# 3-channel_geo_amplifier.net
KiCad netlist of a schematic drawn in EAGLE
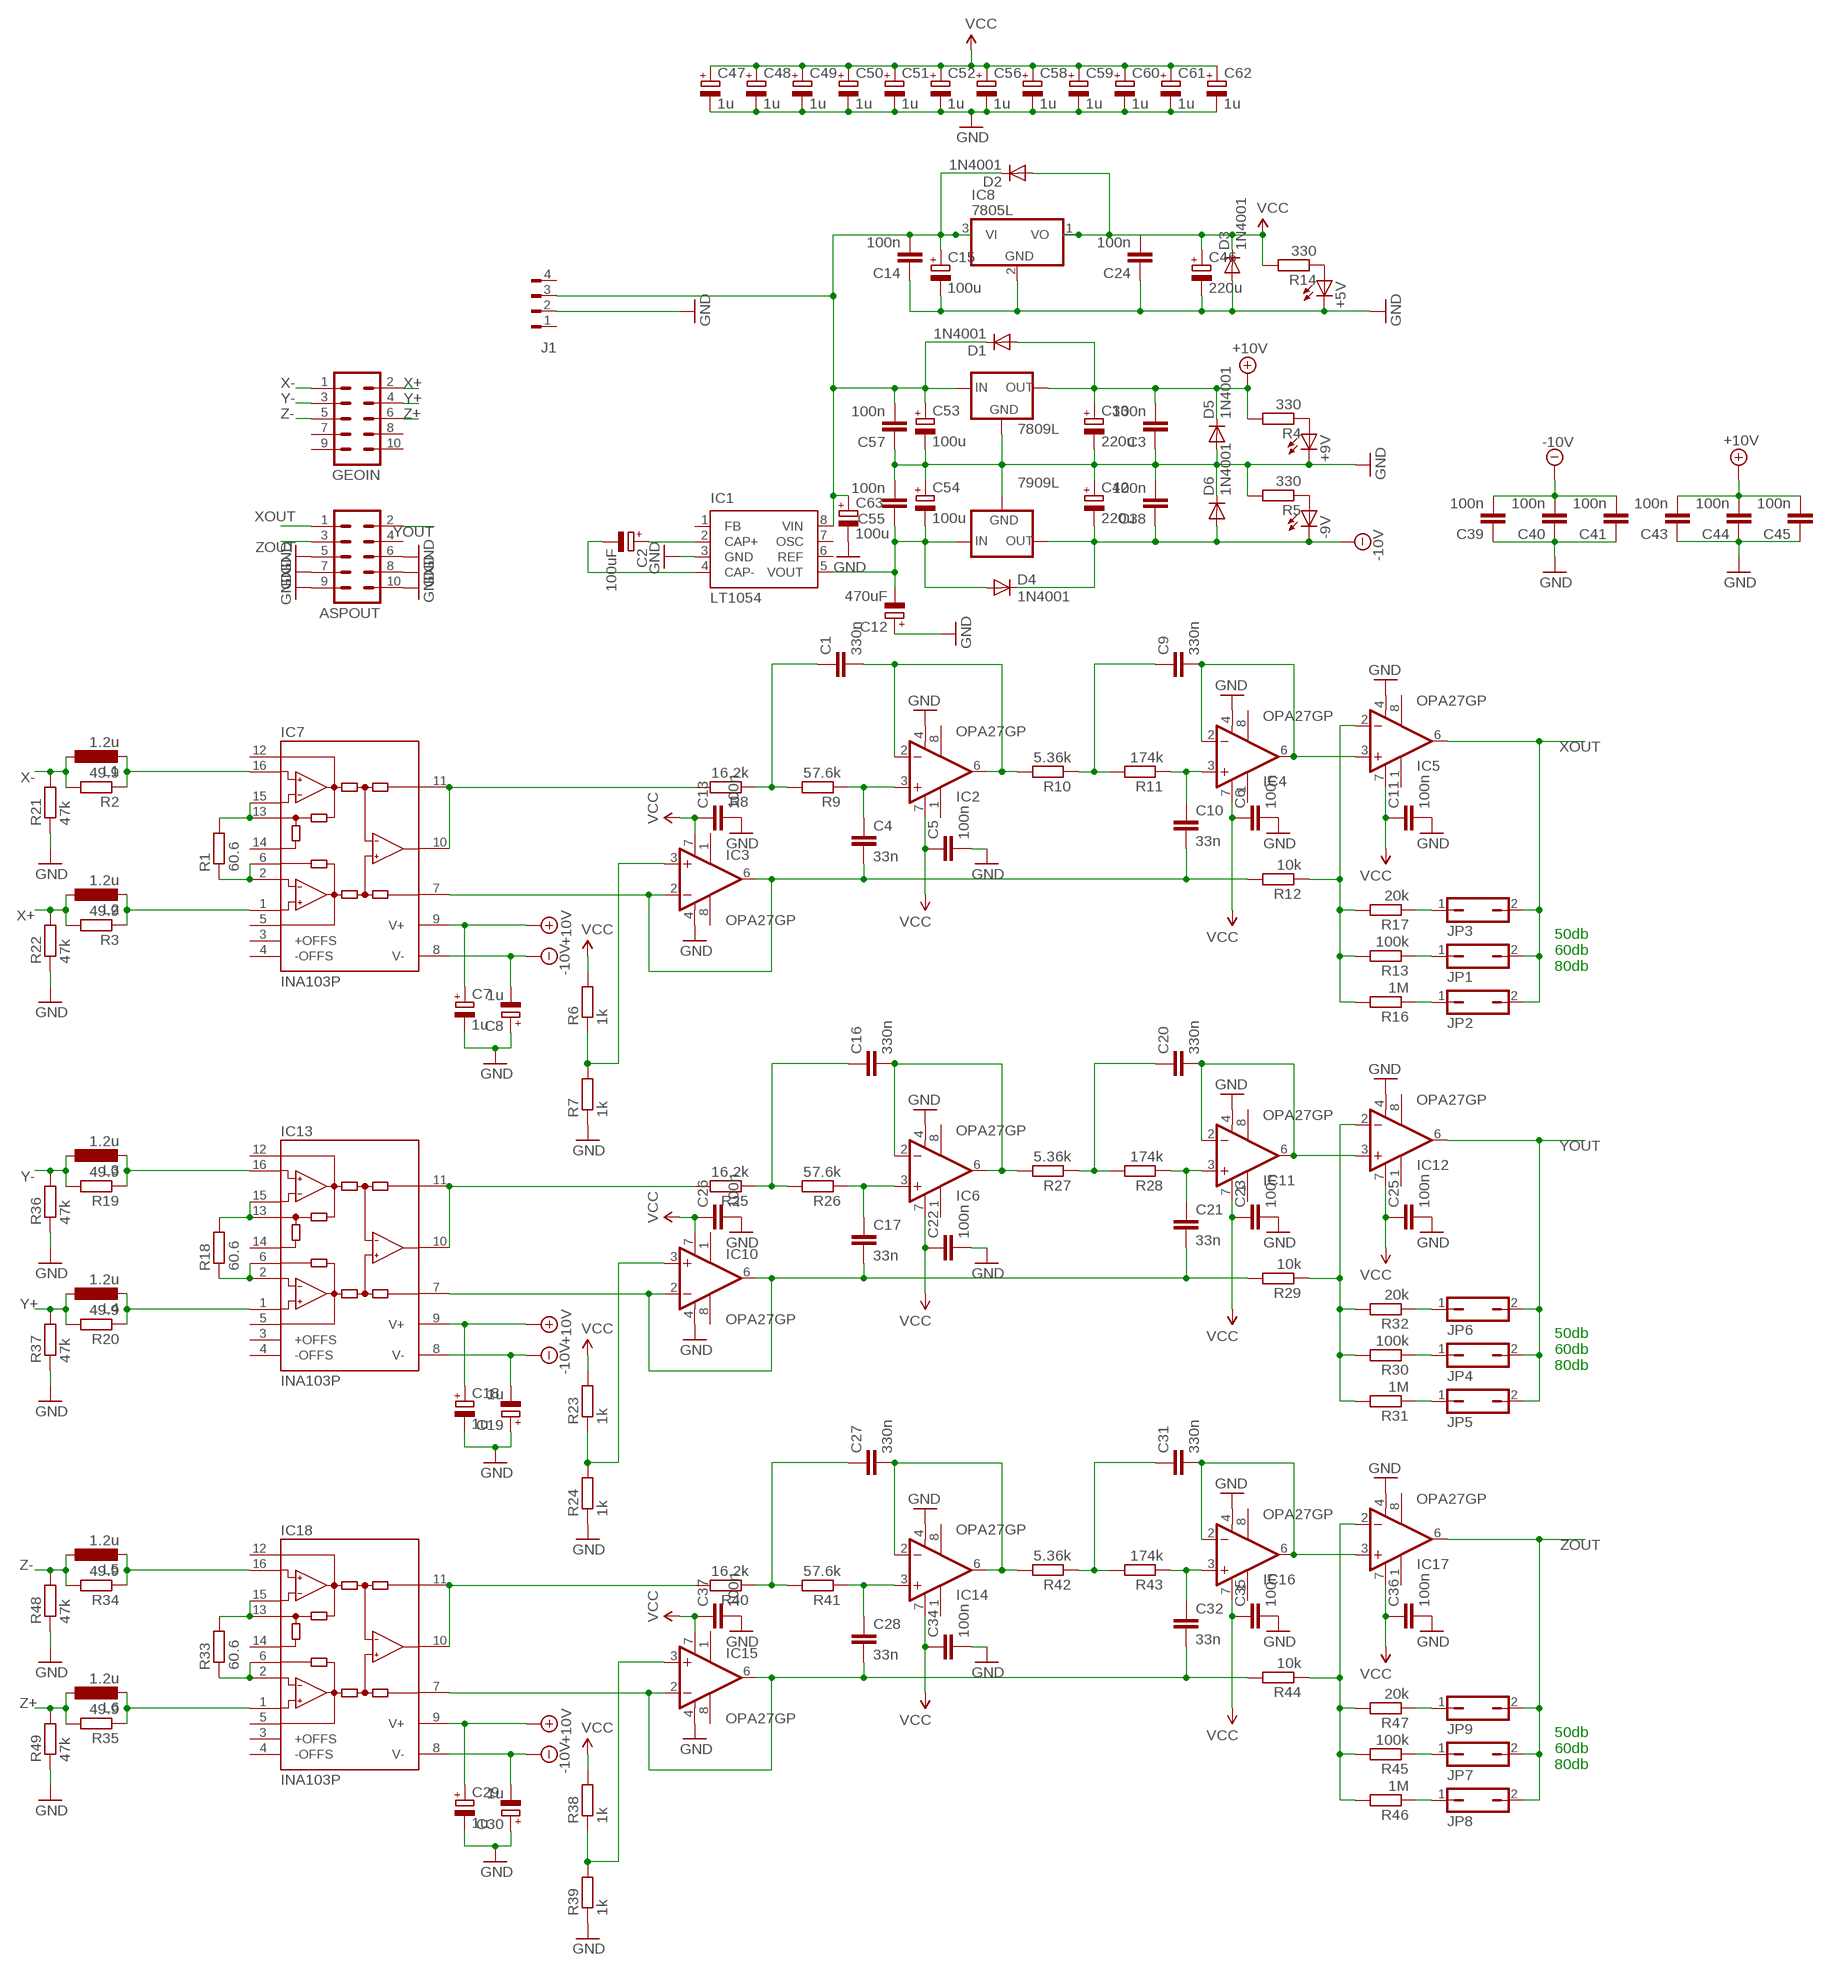
[diagram p0: schematic, sheet 1]

(export (version "E")
  (design (tool "Eeschema 10.0.6"))
  (components
    (comp (ref "+5V")
      (value "LED3MM")
      (footprint "eagle-import:LED3MM")
      (libsource (lib "eagle-import") (part "LED3MM"))
    )
    (comp (ref "+9V")
      (value "LED3MM")
      (footprint "eagle-import:LED3MM")
      (libsource (lib "eagle-import") (part "LED3MM"))
    )
    (comp (ref "-9V")
      (value "LED3MM")
      (footprint "eagle-import:LED3MM")
      (libsource (lib "eagle-import") (part "LED3MM"))
    )
    (comp (ref "7809L")
      (value "78LXX")
      (footprint "eagle-import:78LXX")
      (libsource (lib "eagle-import") (part "78LXX"))
    )
    (comp (ref "7909L")
      (value "79LXX")
      (footprint "eagle-import:79LXX")
      (libsource (lib "eagle-import") (part "79LXX"))
    )
    (comp (ref "ASPOUT")
      (value "ML10")
      (footprint "eagle-import:ML10")
      (libsource (lib "eagle-import") (part "ML10"))
    )
    (comp (ref "C1")
      (value "330n")
      (footprint "eagle-import:C050-025X075")
      (libsource (lib "eagle-import") (part "C-EU050-025X075"))
    )
    (comp (ref "C2")
      (value "100uF")
      (footprint "eagle-import:E2,5-7")
      (libsource (lib "eagle-import") (part "CPOL-EUE2.5-7"))
    )
    (comp (ref "C3")
      (value "100n")
      (footprint "eagle-import:C050-025X075")
      (libsource (lib "eagle-import") (part "C-EU050-025X075"))
    )
    (comp (ref "C4")
      (value "33n")
      (footprint "eagle-import:C050-025X075")
      (libsource (lib "eagle-import") (part "C-EU050-025X075"))
    )
    (comp (ref "C5")
      (value "100n")
      (footprint "eagle-import:C050-025X075")
      (libsource (lib "eagle-import") (part "C-EU050-025X075"))
    )
    (comp (ref "C6")
      (value "100n")
      (footprint "eagle-import:C050-025X075")
      (libsource (lib "eagle-import") (part "C-EU050-025X075"))
    )
    (comp (ref "C7")
      (value "1u")
      (footprint "eagle-import:B45181A")
      (libsource (lib "eagle-import") (part "CPOL-EUB45181A"))
    )
    (comp (ref "C8")
      (value "1u")
      (footprint "eagle-import:B45181A")
      (libsource (lib "eagle-import") (part "CPOL-EUB45181A"))
    )
    (comp (ref "C9")
      (value "330n")
      (footprint "eagle-import:C050-025X075")
      (libsource (lib "eagle-import") (part "C-EU050-025X075"))
    )
    (comp (ref "C10")
      (value "33n")
      (footprint "eagle-import:C050-025X075")
      (libsource (lib "eagle-import") (part "C-EU050-025X075"))
    )
    (comp (ref "C11")
      (value "100n")
      (footprint "eagle-import:C050-025X075")
      (libsource (lib "eagle-import") (part "C-EU050-025X075"))
    )
    (comp (ref "C12")
      (value "470uF")
      (footprint "eagle-import:E5-8,5")
      (libsource (lib "eagle-import") (part "CPOL-EUE5-8.5"))
    )
    (comp (ref "C13")
      (value "100n")
      (footprint "eagle-import:C050-025X075")
      (libsource (lib "eagle-import") (part "C-EU050-025X075"))
    )
    (comp (ref "C14")
      (value "100n")
      (footprint "eagle-import:C050-025X075")
      (libsource (lib "eagle-import") (part "C-EU050-025X075"))
    )
    (comp (ref "C15")
      (value "100u")
      (footprint "eagle-import:E2,5-7")
      (libsource (lib "eagle-import") (part "CPOL-EUE2.5-7"))
    )
    (comp (ref "C16")
      (value "330n")
      (footprint "eagle-import:C050-025X075")
      (libsource (lib "eagle-import") (part "C-EU050-025X075"))
    )
    (comp (ref "C17")
      (value "33n")
      (footprint "eagle-import:C050-025X075")
      (libsource (lib "eagle-import") (part "C-EU050-025X075"))
    )
    (comp (ref "C18")
      (value "1u")
      (footprint "eagle-import:B45181A")
      (libsource (lib "eagle-import") (part "CPOL-EUB45181A"))
    )
    (comp (ref "C19")
      (value "1u")
      (footprint "eagle-import:B45181A")
      (libsource (lib "eagle-import") (part "CPOL-EUB45181A"))
    )
    (comp (ref "C20")
      (value "330n")
      (footprint "eagle-import:C050-025X075")
      (libsource (lib "eagle-import") (part "C-EU050-025X075"))
    )
    (comp (ref "C21")
      (value "33n")
      (footprint "eagle-import:C050-025X075")
      (libsource (lib "eagle-import") (part "C-EU050-025X075"))
    )
    (comp (ref "C22")
      (value "100n")
      (footprint "eagle-import:C050-025X075")
      (libsource (lib "eagle-import") (part "C-EU050-025X075"))
    )
    (comp (ref "C23")
      (value "100n")
      (footprint "eagle-import:C050-025X075")
      (libsource (lib "eagle-import") (part "C-EU050-025X075"))
    )
    (comp (ref "C24")
      (value "100n")
      (footprint "eagle-import:C050-025X075")
      (libsource (lib "eagle-import") (part "C-EU050-025X075"))
    )
    (comp (ref "C25")
      (value "100n")
      (footprint "eagle-import:C050-025X075")
      (libsource (lib "eagle-import") (part "C-EU050-025X075"))
    )
    (comp (ref "C26")
      (value "100n")
      (footprint "eagle-import:C050-025X075")
      (libsource (lib "eagle-import") (part "C-EU050-025X075"))
    )
    (comp (ref "C27")
      (value "330n")
      (footprint "eagle-import:C050-025X075")
      (libsource (lib "eagle-import") (part "C-EU050-025X075"))
    )
    (comp (ref "C28")
      (value "33n")
      (footprint "eagle-import:C050-025X075")
      (libsource (lib "eagle-import") (part "C-EU050-025X075"))
    )
    (comp (ref "C29")
      (value "1u")
      (footprint "eagle-import:B45181A")
      (libsource (lib "eagle-import") (part "CPOL-EUB45181A"))
    )
    (comp (ref "C30")
      (value "1u")
      (footprint "eagle-import:B45181A")
      (libsource (lib "eagle-import") (part "CPOL-EUB45181A"))
    )
    (comp (ref "C31")
      (value "330n")
      (footprint "eagle-import:C050-025X075")
      (libsource (lib "eagle-import") (part "C-EU050-025X075"))
    )
    (comp (ref "C32")
      (value "33n")
      (footprint "eagle-import:C050-025X075")
      (libsource (lib "eagle-import") (part "C-EU050-025X075"))
    )
    (comp (ref "C33")
      (value "220u")
      (footprint "eagle-import:E2,5-5")
      (libsource (lib "eagle-import") (part "CPOL-EUE2.5-5"))
    )
    (comp (ref "C34")
      (value "100n")
      (footprint "eagle-import:C050-025X075")
      (libsource (lib "eagle-import") (part "C-EU050-025X075"))
    )
    (comp (ref "C35")
      (value "100n")
      (footprint "eagle-import:C050-025X075")
      (libsource (lib "eagle-import") (part "C-EU050-025X075"))
    )
    (comp (ref "C36")
      (value "100n")
      (footprint "eagle-import:C050-025X075")
      (libsource (lib "eagle-import") (part "C-EU050-025X075"))
    )
    (comp (ref "C37")
      (value "100n")
      (footprint "eagle-import:C050-025X075")
      (libsource (lib "eagle-import") (part "C-EU050-025X075"))
    )
    (comp (ref "C38")
      (value "100n")
      (footprint "eagle-import:C050-025X075")
      (libsource (lib "eagle-import") (part "C-EU050-025X075"))
    )
    (comp (ref "C39")
      (value "100n")
      (footprint "eagle-import:C050-025X075")
      (libsource (lib "eagle-import") (part "C-EU050-025X075"))
    )
    (comp (ref "C40")
      (value "100n")
      (footprint "eagle-import:C050-025X075")
      (libsource (lib "eagle-import") (part "C-EU050-025X075"))
    )
    (comp (ref "C41")
      (value "100n")
      (footprint "eagle-import:C050-025X075")
      (libsource (lib "eagle-import") (part "C-EU050-025X075"))
    )
    (comp (ref "C42")
      (value "220u")
      (footprint "eagle-import:E2,5-5")
      (libsource (lib "eagle-import") (part "CPOL-EUE2.5-5"))
    )
    (comp (ref "C43")
      (value "100n")
      (footprint "eagle-import:C050-025X075")
      (libsource (lib "eagle-import") (part "C-EU050-025X075"))
    )
    (comp (ref "C44")
      (value "100n")
      (footprint "eagle-import:C050-025X075")
      (libsource (lib "eagle-import") (part "C-EU050-025X075"))
    )
    (comp (ref "C45")
      (value "100n")
      (footprint "eagle-import:C050-025X075")
      (libsource (lib "eagle-import") (part "C-EU050-025X075"))
    )
    (comp (ref "C46")
      (value "220u")
      (footprint "eagle-import:E2,5-7")
      (libsource (lib "eagle-import") (part "CPOL-EUE2.5-7"))
    )
    (comp (ref "C47")
      (value "1u")
      (footprint "eagle-import:B45181A")
      (libsource (lib "eagle-import") (part "CPOL-EUB45181A"))
    )
    (comp (ref "C48")
      (value "1u")
      (footprint "eagle-import:B45181A")
      (libsource (lib "eagle-import") (part "CPOL-EUB45181A"))
    )
    (comp (ref "C49")
      (value "1u")
      (footprint "eagle-import:B45181A")
      (libsource (lib "eagle-import") (part "CPOL-EUB45181A"))
    )
    (comp (ref "C50")
      (value "1u")
      (footprint "eagle-import:B45181A")
      (libsource (lib "eagle-import") (part "CPOL-EUB45181A"))
    )
    (comp (ref "C51")
      (value "1u")
      (footprint "eagle-import:B45181A")
      (libsource (lib "eagle-import") (part "CPOL-EUB45181A"))
    )
    (comp (ref "C52")
      (value "1u")
      (footprint "eagle-import:B45181A")
      (libsource (lib "eagle-import") (part "CPOL-EUB45181A"))
    )
    (comp (ref "C53")
      (value "100u")
      (footprint "eagle-import:E2,5-5")
      (libsource (lib "eagle-import") (part "CPOL-EUE2.5-5"))
    )
    (comp (ref "C54")
      (value "100u")
      (footprint "eagle-import:E2,5-5")
      (libsource (lib "eagle-import") (part "CPOL-EUE2.5-5"))
    )
    (comp (ref "C55")
      (value "100n")
      (footprint "eagle-import:C050-025X075")
      (libsource (lib "eagle-import") (part "C-EU050-025X075"))
    )
    (comp (ref "C56")
      (value "1u")
      (footprint "eagle-import:B45181A")
      (libsource (lib "eagle-import") (part "CPOL-EUB45181A"))
    )
    (comp (ref "C57")
      (value "100n")
      (footprint "eagle-import:C050-025X075")
      (libsource (lib "eagle-import") (part "C-EU050-025X075"))
    )
    (comp (ref "C58")
      (value "1u")
      (footprint "eagle-import:B45181A")
      (libsource (lib "eagle-import") (part "CPOL-EUB45181A"))
    )
    (comp (ref "C59")
      (value "1u")
      (footprint "eagle-import:B45181A")
      (libsource (lib "eagle-import") (part "CPOL-EUB45181A"))
    )
    (comp (ref "C60")
      (value "1u")
      (footprint "eagle-import:B45181A")
      (libsource (lib "eagle-import") (part "CPOL-EUB45181A"))
    )
    (comp (ref "C61")
      (value "1u")
      (footprint "eagle-import:B45181A")
      (libsource (lib "eagle-import") (part "CPOL-EUB45181A"))
    )
    (comp (ref "C62")
      (value "1u")
      (footprint "eagle-import:B45181A")
      (libsource (lib "eagle-import") (part "CPOL-EUB45181A"))
    )
    (comp (ref "C63")
      (value "100u")
      (footprint "eagle-import:E2,5-5")
      (libsource (lib "eagle-import") (part "CPOL-EUE2.5-5"))
    )
    (comp (ref "D1")
      (value "1N4001")
      (footprint "eagle-import:DO41-10")
      (libsource (lib "eagle-import") (part "1N4004"))
    )
    (comp (ref "D2")
      (value "1N4001")
      (footprint "eagle-import:DO41-10")
      (libsource (lib "eagle-import") (part "1N4004"))
    )
    (comp (ref "D3")
      (value "1N4001")
      (footprint "eagle-import:DO41-10")
      (libsource (lib "eagle-import") (part "1N4004"))
    )
    (comp (ref "D4")
      (value "1N4001")
      (footprint "eagle-import:DO41-10")
      (libsource (lib "eagle-import") (part "1N4004"))
    )
    (comp (ref "D5")
      (value "1N4001")
      (footprint "eagle-import:DO41-10")
      (libsource (lib "eagle-import") (part "1N4004"))
    )
    (comp (ref "D6")
      (value "1N4001")
      (footprint "eagle-import:DO41-10")
      (libsource (lib "eagle-import") (part "1N4004"))
    )
    (comp (ref "GEOIN")
      (value "ML10")
      (footprint "eagle-import:ML10")
      (libsource (lib "eagle-import") (part "ML10"))
    )
    (comp (ref "IC1")
      (value "LT1054")
      (footprint "eagle-import:DIL8")
      (libsource (lib "eagle-import") (part "LT1054"))
    )
    (comp (ref "IC2")
      (value "OPA27GP")
      (footprint "eagle-import:DIL08")
      (libsource (lib "eagle-import") (part "OPA?GP27"))
    )
    (comp (ref "IC3")
      (value "OPA27GP")
      (footprint "eagle-import:DIL08")
      (libsource (lib "eagle-import") (part "OPA?GP27"))
    )
    (comp (ref "IC4")
      (value "OPA27GP")
      (footprint "eagle-import:DIL08")
      (libsource (lib "eagle-import") (part "OPA?GP27"))
    )
    (comp (ref "IC5")
      (value "OPA27GP")
      (footprint "eagle-import:DIL08")
      (libsource (lib "eagle-import") (part "OPA?GP27"))
    )
    (comp (ref "IC6")
      (value "OPA27GP")
      (footprint "eagle-import:DIL08")
      (libsource (lib "eagle-import") (part "OPA?GP27"))
    )
    (comp (ref "IC7")
      (value "INA103P")
      (footprint "eagle-import:DIL16")
      (fields (field (name "MF") "TEXAS INSTRUMENTS") (field (name "MPN") "INA103KP"))
      (libsource (lib "eagle-import") (part "INA103P"))
    )
    (comp (ref "IC8")
      (value "7805L")
      (footprint "eagle-import:TO92")
      (libsource (lib "eagle-import") (part "78L05"))
    )
    (comp (ref "IC10")
      (value "OPA27GP")
      (footprint "eagle-import:DIL08")
      (libsource (lib "eagle-import") (part "OPA?GP27"))
    )
    (comp (ref "IC11")
      (value "OPA27GP")
      (footprint "eagle-import:DIL08")
      (libsource (lib "eagle-import") (part "OPA?GP27"))
    )
    (comp (ref "IC12")
      (value "OPA27GP")
      (footprint "eagle-import:DIL08")
      (libsource (lib "eagle-import") (part "OPA?GP27"))
    )
    (comp (ref "IC13")
      (value "INA103P")
      (footprint "eagle-import:DIL16")
      (fields (field (name "MF") "TEXAS INSTRUMENTS") (field (name "MPN") "INA103KP"))
      (libsource (lib "eagle-import") (part "INA103P"))
    )
    (comp (ref "IC14")
      (value "OPA27GP")
      (footprint "eagle-import:DIL08")
      (libsource (lib "eagle-import") (part "OPA?GP27"))
    )
    (comp (ref "IC15")
      (value "OPA27GP")
      (footprint "eagle-import:DIL08")
      (libsource (lib "eagle-import") (part "OPA?GP27"))
    )
    (comp (ref "IC16")
      (value "OPA27GP")
      (footprint "eagle-import:DIL08")
      (libsource (lib "eagle-import") (part "OPA?GP27"))
    )
    (comp (ref "IC17")
      (value "OPA27GP")
      (footprint "eagle-import:DIL08")
      (libsource (lib "eagle-import") (part "OPA?GP27"))
    )
    (comp (ref "IC18")
      (value "INA103P")
      (footprint "eagle-import:DIL16")
      (fields (field (name "MF") "TEXAS INSTRUMENTS") (field (name "MPN") "INA103KP"))
      (libsource (lib "eagle-import") (part "INA103P"))
    )
    (comp (ref "J1")
      (value "FLOP-4W827001")
      (footprint "eagle-import:827001")
      (libsource (lib "eagle-import") (part "FLOP-4W827001"))
    )
    (comp (ref "JP1")
      (value "JP1Q")
      (footprint "eagle-import:JP1")
      (libsource (lib "eagle-import") (part "JP1Q"))
    )
    (comp (ref "JP2")
      (value "JP1Q")
      (footprint "eagle-import:JP1")
      (libsource (lib "eagle-import") (part "JP1Q"))
    )
    (comp (ref "JP3")
      (value "JP1Q")
      (footprint "eagle-import:JP1")
      (libsource (lib "eagle-import") (part "JP1Q"))
    )
    (comp (ref "JP4")
      (value "JP1Q")
      (footprint "eagle-import:JP1")
      (libsource (lib "eagle-import") (part "JP1Q"))
    )
    (comp (ref "JP5")
      (value "JP1Q")
      (footprint "eagle-import:JP1")
      (libsource (lib "eagle-import") (part "JP1Q"))
    )
    (comp (ref "JP6")
      (value "JP1Q")
      (footprint "eagle-import:JP1")
      (libsource (lib "eagle-import") (part "JP1Q"))
    )
    (comp (ref "JP7")
      (value "JP1Q")
      (footprint "eagle-import:JP1")
      (libsource (lib "eagle-import") (part "JP1Q"))
    )
    (comp (ref "JP8")
      (value "JP1Q")
      (footprint "eagle-import:JP1")
      (libsource (lib "eagle-import") (part "JP1Q"))
    )
    (comp (ref "JP9")
      (value "JP1Q")
      (footprint "eagle-import:JP1")
      (libsource (lib "eagle-import") (part "JP1Q"))
    )
    (comp (ref "L1")
      (value "1.2u")
      (footprint "eagle-import:0207_10")
      (libsource (lib "eagle-import") (part "L-EU0207/10"))
    )
    (comp (ref "L2")
      (value "1.2u")
      (footprint "eagle-import:0207_10")
      (libsource (lib "eagle-import") (part "L-EU0207/10"))
    )
    (comp (ref "L3")
      (value "1.2u")
      (footprint "eagle-import:0207_10")
      (libsource (lib "eagle-import") (part "L-EU0207/10"))
    )
    (comp (ref "L4")
      (value "1.2u")
      (footprint "eagle-import:0207_10")
      (libsource (lib "eagle-import") (part "L-EU0207/10"))
    )
    (comp (ref "L5")
      (value "1.2u")
      (footprint "eagle-import:0207_10")
      (libsource (lib "eagle-import") (part "L-EU0207/10"))
    )
    (comp (ref "L6")
      (value "1.2u")
      (footprint "eagle-import:0207_10")
      (libsource (lib "eagle-import") (part "L-EU0207/10"))
    )
    (comp (ref "R1")
      (value "60.6")
      (footprint "eagle-import:0207_10")
      (libsource (lib "eagle-import") (part "R-EU_0207/10"))
    )
    (comp (ref "R2")
      (value "49.9")
      (footprint "eagle-import:0207_10")
      (libsource (lib "eagle-import") (part "R-EU_0207/10"))
    )
    (comp (ref "R3")
      (value "49.9")
      (footprint "eagle-import:0207_10")
      (libsource (lib "eagle-import") (part "R-EU_0207/10"))
    )
    (comp (ref "R4")
      (value "330")
      (footprint "eagle-import:0207_10")
      (libsource (lib "eagle-import") (part "R-EU_0207/10"))
    )
    (comp (ref "R5")
      (value "330")
      (footprint "eagle-import:0207_10")
      (libsource (lib "eagle-import") (part "R-EU_0207/10"))
    )
    (comp (ref "R6")
      (value "1k")
      (footprint "eagle-import:0207_10")
      (libsource (lib "eagle-import") (part "R-EU_0207/10"))
    )
    (comp (ref "R7")
      (value "1k")
      (footprint "eagle-import:0207_10")
      (libsource (lib "eagle-import") (part "R-EU_0207/10"))
    )
    (comp (ref "R8")
      (value "16.2k")
      (footprint "eagle-import:0207_10")
      (libsource (lib "eagle-import") (part "R-EU_0207/10"))
    )
    (comp (ref "R9")
      (value "57.6k")
      (footprint "eagle-import:0207_10")
      (libsource (lib "eagle-import") (part "R-EU_0207/10"))
    )
    (comp (ref "R10")
      (value "5.36k")
      (footprint "eagle-import:0207_10")
      (libsource (lib "eagle-import") (part "R-EU_0207/10"))
    )
    (comp (ref "R11")
      (value "174k")
      (footprint "eagle-import:0207_10")
      (libsource (lib "eagle-import") (part "R-EU_0207/10"))
    )
    (comp (ref "R12")
      (value "10k")
      (footprint "eagle-import:0207_10")
      (libsource (lib "eagle-import") (part "R-EU_0207/10"))
    )
    (comp (ref "R13")
      (value "100k")
      (footprint "eagle-import:0207_10")
      (libsource (lib "eagle-import") (part "R-EU_0207/10"))
    )
    (comp (ref "R14")
      (value "330")
      (footprint "eagle-import:0207_10")
      (libsource (lib "eagle-import") (part "R-EU_0207/10"))
    )
    (comp (ref "R16")
      (value "1M")
      (footprint "eagle-import:0207_10")
      (libsource (lib "eagle-import") (part "R-EU_0207/10"))
    )
    (comp (ref "R17")
      (value "20k")
      (footprint "eagle-import:0207_10")
      (libsource (lib "eagle-import") (part "R-EU_0207/10"))
    )
    (comp (ref "R18")
      (value "60.6")
      (footprint "eagle-import:0207_10")
      (libsource (lib "eagle-import") (part "R-EU_0207/10"))
    )
    (comp (ref "R19")
      (value "49.9")
      (footprint "eagle-import:0207_10")
      (libsource (lib "eagle-import") (part "R-EU_0207/10"))
    )
    (comp (ref "R20")
      (value "49.9")
      (footprint "eagle-import:0207_10")
      (libsource (lib "eagle-import") (part "R-EU_0207/10"))
    )
    (comp (ref "R21")
      (value "47k")
      (footprint "eagle-import:0207_10")
      (libsource (lib "eagle-import") (part "R-EU_0207/10"))
    )
    (comp (ref "R22")
      (value "47k")
      (footprint "eagle-import:0207_10")
      (libsource (lib "eagle-import") (part "R-EU_0207/10"))
    )
    (comp (ref "R23")
      (value "1k")
      (footprint "eagle-import:0207_10")
      (libsource (lib "eagle-import") (part "R-EU_0207/10"))
    )
    (comp (ref "R24")
      (value "1k")
      (footprint "eagle-import:0207_10")
      (libsource (lib "eagle-import") (part "R-EU_0207/10"))
    )
    (comp (ref "R25")
      (value "16.2k")
      (footprint "eagle-import:0207_10")
      (libsource (lib "eagle-import") (part "R-EU_0207/10"))
    )
    (comp (ref "R26")
      (value "57.6k")
      (footprint "eagle-import:0207_10")
      (libsource (lib "eagle-import") (part "R-EU_0207/10"))
    )
    (comp (ref "R27")
      (value "5.36k")
      (footprint "eagle-import:0207_10")
      (libsource (lib "eagle-import") (part "R-EU_0207/10"))
    )
    (comp (ref "R28")
      (value "174k")
      (footprint "eagle-import:0207_10")
      (libsource (lib "eagle-import") (part "R-EU_0207/10"))
    )
    (comp (ref "R29")
      (value "10k")
      (footprint "eagle-import:0207_10")
      (libsource (lib "eagle-import") (part "R-EU_0207/10"))
    )
    (comp (ref "R30")
      (value "100k")
      (footprint "eagle-import:0207_10")
      (libsource (lib "eagle-import") (part "R-EU_0207/10"))
    )
    (comp (ref "R31")
      (value "1M")
      (footprint "eagle-import:0207_10")
      (libsource (lib "eagle-import") (part "R-EU_0207/10"))
    )
    (comp (ref "R32")
      (value "20k")
      (footprint "eagle-import:0207_10")
      (libsource (lib "eagle-import") (part "R-EU_0207/10"))
    )
    (comp (ref "R33")
      (value "60.6")
      (footprint "eagle-import:0207_10")
      (libsource (lib "eagle-import") (part "R-EU_0207/10"))
    )
    (comp (ref "R34")
      (value "49.9")
      (footprint "eagle-import:0207_10")
      (libsource (lib "eagle-import") (part "R-EU_0207/10"))
    )
    (comp (ref "R35")
      (value "49.9")
      (footprint "eagle-import:0207_10")
      (libsource (lib "eagle-import") (part "R-EU_0207/10"))
    )
    (comp (ref "R36")
      (value "47k")
      (footprint "eagle-import:0207_10")
      (libsource (lib "eagle-import") (part "R-EU_0207/10"))
    )
    (comp (ref "R37")
      (value "47k")
      (footprint "eagle-import:0207_10")
      (libsource (lib "eagle-import") (part "R-EU_0207/10"))
    )
    (comp (ref "R38")
      (value "1k")
      (footprint "eagle-import:0207_10")
      (libsource (lib "eagle-import") (part "R-EU_0207/10"))
    )
    (comp (ref "R39")
      (value "1k")
      (footprint "eagle-import:0207_10")
      (libsource (lib "eagle-import") (part "R-EU_0207/10"))
    )
    (comp (ref "R40")
      (value "16.2k")
      (footprint "eagle-import:0207_10")
      (libsource (lib "eagle-import") (part "R-EU_0207/10"))
    )
    (comp (ref "R41")
      (value "57.6k")
      (footprint "eagle-import:0207_10")
      (libsource (lib "eagle-import") (part "R-EU_0207/10"))
    )
    (comp (ref "R42")
      (value "5.36k")
      (footprint "eagle-import:0207_10")
      (libsource (lib "eagle-import") (part "R-EU_0207/10"))
    )
    (comp (ref "R43")
      (value "174k")
      (footprint "eagle-import:0207_10")
      (libsource (lib "eagle-import") (part "R-EU_0207/10"))
    )
    (comp (ref "R44")
      (value "10k")
      (footprint "eagle-import:0207_10")
      (libsource (lib "eagle-import") (part "R-EU_0207/10"))
    )
    (comp (ref "R45")
      (value "100k")
      (footprint "eagle-import:0207_10")
      (libsource (lib "eagle-import") (part "R-EU_0207/10"))
    )
    (comp (ref "R46")
      (value "1M")
      (footprint "eagle-import:0207_10")
      (libsource (lib "eagle-import") (part "R-EU_0207/10"))
    )
    (comp (ref "R47")
      (value "20k")
      (footprint "eagle-import:0207_10")
      (libsource (lib "eagle-import") (part "R-EU_0207/10"))
    )
    (comp (ref "R48")
      (value "47k")
      (footprint "eagle-import:0207_10")
      (libsource (lib "eagle-import") (part "R-EU_0207/10"))
    )
    (comp (ref "R49")
      (value "47k")
      (footprint "eagle-import:0207_10")
      (libsource (lib "eagle-import") (part "R-EU_0207/10"))
    )
  )
  (nets
    (net (code "1") (name "+10V") (class "Default")
      (node (ref "7809L") (pin "OUT") (pinfunction "OUT_OUT") (pintype "passive"))
      (node (ref "C18") (pin "+") (pinfunction "+_+") (pintype "passive"))
      (node (ref "C29") (pin "+") (pinfunction "+_+") (pintype "passive"))
      (node (ref "C3") (pin "2") (pinfunction "2_2") (pintype "passive"))
      (node (ref "C33") (pin "+") (pinfunction "+_+") (pintype "passive"))
      (node (ref "C43") (pin "2") (pinfunction "2_2") (pintype "passive"))
      (node (ref "C44") (pin "2") (pinfunction "2_2") (pintype "passive"))
      (node (ref "C45") (pin "2") (pinfunction "2_2") (pintype "passive"))
      (node (ref "C7") (pin "+") (pinfunction "+_+") (pintype "passive"))
      (node (ref "D1") (pin "A") (pinfunction "A_A") (pintype "passive"))
      (node (ref "D5") (pin "C") (pinfunction "C_C") (pintype "passive"))
      (node (ref "IC13") (pin "9") (pinfunction "V+_9") (pintype "power_in"))
      (node (ref "IC18") (pin "9") (pinfunction "V+_9") (pintype "power_in"))
      (node (ref "IC7") (pin "9") (pinfunction "V+_9") (pintype "power_in"))
      (node (ref "R4") (pin "2") (pinfunction "2_2") (pintype "passive"))
    )
    (net (code "2") (name "-10V") (class "Default")
      (node (ref "-9V") (pin "K") (pinfunction "C_K") (pintype "passive"))
      (node (ref "7909L") (pin "OUT") (pinfunction "OUT_OUT") (pintype "passive"))
      (node (ref "C19") (pin "-") (pinfunction "-_-") (pintype "passive"))
      (node (ref "C30") (pin "-") (pinfunction "-_-") (pintype "passive"))
      (node (ref "C38") (pin "1") (pinfunction "1_1") (pintype "passive"))
      (node (ref "C39") (pin "2") (pinfunction "2_2") (pintype "passive"))
      (node (ref "C40") (pin "2") (pinfunction "2_2") (pintype "passive"))
      (node (ref "C41") (pin "2") (pinfunction "2_2") (pintype "passive"))
      (node (ref "C42") (pin "-") (pinfunction "-_-") (pintype "passive"))
      (node (ref "C8") (pin "-") (pinfunction "-_-") (pintype "passive"))
      (node (ref "D4") (pin "C") (pinfunction "C_C") (pintype "passive"))
      (node (ref "D6") (pin "A") (pinfunction "A_A") (pintype "passive"))
      (node (ref "IC13") (pin "8") (pinfunction "V-_8") (pintype "power_in"))
      (node (ref "IC18") (pin "8") (pinfunction "V-_8") (pintype "power_in"))
      (node (ref "IC7") (pin "8") (pinfunction "V-_8") (pintype "power_in"))
    )
    (net (code "3") (name "/X+") (class "Default")
      (node (ref "GEOIN") (pin "2") (pinfunction "2_2") (pintype "passive"))
      (node (ref "L2") (pin "1") (pinfunction "1_1") (pintype "passive"))
      (node (ref "R22") (pin "2") (pinfunction "2_2") (pintype "passive"))
      (node (ref "R3") (pin "2") (pinfunction "2_2") (pintype "passive"))
    )
    (net (code "4") (name "/X-") (class "Default")
      (node (ref "GEOIN") (pin "1") (pinfunction "1_1") (pintype "passive"))
      (node (ref "L1") (pin "1") (pinfunction "1_1") (pintype "passive"))
      (node (ref "R2") (pin "2") (pinfunction "2_2") (pintype "passive"))
      (node (ref "R21") (pin "2") (pinfunction "2_2") (pintype "passive"))
    )
    (net (code "5") (name "/XOUT") (class "Default")
      (node (ref "ASPOUT") (pin "1") (pinfunction "1_1") (pintype "passive"))
      (node (ref "IC5") (pin "6") (pinfunction "OUT_6") (pintype "output"))
      (node (ref "JP1") (pin "2") (pinfunction "2_2") (pintype "passive"))
      (node (ref "JP2") (pin "2") (pinfunction "2_2") (pintype "passive"))
      (node (ref "JP3") (pin "2") (pinfunction "2_2") (pintype "passive"))
    )
    (net (code "6") (name "/Y+") (class "Default")
      (node (ref "GEOIN") (pin "4") (pinfunction "4_4") (pintype "passive"))
      (node (ref "L4") (pin "1") (pinfunction "1_1") (pintype "passive"))
      (node (ref "R20") (pin "2") (pinfunction "2_2") (pintype "passive"))
      (node (ref "R37") (pin "2") (pinfunction "2_2") (pintype "passive"))
    )
    (net (code "7") (name "/Y-") (class "Default")
      (node (ref "GEOIN") (pin "3") (pinfunction "3_3") (pintype "passive"))
      (node (ref "L3") (pin "1") (pinfunction "1_1") (pintype "passive"))
      (node (ref "R19") (pin "2") (pinfunction "2_2") (pintype "passive"))
      (node (ref "R36") (pin "2") (pinfunction "2_2") (pintype "passive"))
    )
    (net (code "8") (name "/YOUT") (class "Default")
      (node (ref "ASPOUT") (pin "2") (pinfunction "2_2") (pintype "passive"))
      (node (ref "IC12") (pin "6") (pinfunction "OUT_6") (pintype "output"))
      (node (ref "JP4") (pin "2") (pinfunction "2_2") (pintype "passive"))
      (node (ref "JP5") (pin "2") (pinfunction "2_2") (pintype "passive"))
      (node (ref "JP6") (pin "2") (pinfunction "2_2") (pintype "passive"))
    )
    (net (code "9") (name "/Z+") (class "Default")
      (node (ref "GEOIN") (pin "6") (pinfunction "6_6") (pintype "passive"))
      (node (ref "L6") (pin "1") (pinfunction "1_1") (pintype "passive"))
      (node (ref "R35") (pin "2") (pinfunction "2_2") (pintype "passive"))
      (node (ref "R49") (pin "2") (pinfunction "2_2") (pintype "passive"))
    )
    (net (code "10") (name "/Z-") (class "Default")
      (node (ref "GEOIN") (pin "5") (pinfunction "5_5") (pintype "passive"))
      (node (ref "L5") (pin "1") (pinfunction "1_1") (pintype "passive"))
      (node (ref "R34") (pin "2") (pinfunction "2_2") (pintype "passive"))
      (node (ref "R48") (pin "2") (pinfunction "2_2") (pintype "passive"))
    )
    (net (code "11") (name "/ZOUT") (class "Default")
      (node (ref "ASPOUT") (pin "3") (pinfunction "3_3") (pintype "passive"))
      (node (ref "IC17") (pin "6") (pinfunction "OUT_6") (pintype "output"))
      (node (ref "JP7") (pin "2") (pinfunction "2_2") (pintype "passive"))
      (node (ref "JP8") (pin "2") (pinfunction "2_2") (pintype "passive"))
      (node (ref "JP9") (pin "2") (pinfunction "2_2") (pintype "passive"))
    )
    (net (code "12") (name "GND") (class "Default")
      (node (ref "+5V") (pin "K") (pinfunction "C_K") (pintype "passive"))
      (node (ref "+9V") (pin "K") (pinfunction "C_K") (pintype "passive"))
      (node (ref "7809L") (pin "GND") (pinfunction "GND_GND") (pintype "input"))
      (node (ref "7909L") (pin "GND") (pinfunction "GND_GND") (pintype "input"))
      (node (ref "ASPOUT") (pin "10") (pinfunction "10_10") (pintype "passive"))
      (node (ref "ASPOUT") (pin "5") (pinfunction "5_5") (pintype "passive"))
      (node (ref "ASPOUT") (pin "6") (pinfunction "6_6") (pintype "passive"))
      (node (ref "ASPOUT") (pin "7") (pinfunction "7_7") (pintype "passive"))
      (node (ref "ASPOUT") (pin "8") (pinfunction "8_8") (pintype "passive"))
      (node (ref "ASPOUT") (pin "9") (pinfunction "9_9") (pintype "passive"))
      (node (ref "C11") (pin "2") (pinfunction "2_2") (pintype "passive"))
      (node (ref "C12") (pin "+") (pinfunction "+_+") (pintype "passive"))
      (node (ref "C13") (pin "2") (pinfunction "2_2") (pintype "passive"))
      (node (ref "C14") (pin "1") (pinfunction "1_1") (pintype "passive"))
      (node (ref "C15") (pin "-") (pinfunction "-_-") (pintype "passive"))
      (node (ref "C18") (pin "-") (pinfunction "-_-") (pintype "passive"))
      (node (ref "C19") (pin "+") (pinfunction "+_+") (pintype "passive"))
      (node (ref "C22") (pin "2") (pinfunction "2_2") (pintype "passive"))
      (node (ref "C23") (pin "2") (pinfunction "2_2") (pintype "passive"))
      (node (ref "C24") (pin "1") (pinfunction "1_1") (pintype "passive"))
      (node (ref "C25") (pin "2") (pinfunction "2_2") (pintype "passive"))
      (node (ref "C26") (pin "2") (pinfunction "2_2") (pintype "passive"))
      (node (ref "C29") (pin "-") (pinfunction "-_-") (pintype "passive"))
      (node (ref "C3") (pin "1") (pinfunction "1_1") (pintype "passive"))
      (node (ref "C30") (pin "+") (pinfunction "+_+") (pintype "passive"))
      (node (ref "C33") (pin "-") (pinfunction "-_-") (pintype "passive"))
      (node (ref "C34") (pin "2") (pinfunction "2_2") (pintype "passive"))
      (node (ref "C35") (pin "2") (pinfunction "2_2") (pintype "passive"))
      (node (ref "C36") (pin "2") (pinfunction "2_2") (pintype "passive"))
      (node (ref "C37") (pin "2") (pinfunction "2_2") (pintype "passive"))
      (node (ref "C38") (pin "2") (pinfunction "2_2") (pintype "passive"))
      (node (ref "C39") (pin "1") (pinfunction "1_1") (pintype "passive"))
      (node (ref "C40") (pin "1") (pinfunction "1_1") (pintype "passive"))
      (node (ref "C41") (pin "1") (pinfunction "1_1") (pintype "passive"))
      (node (ref "C42") (pin "+") (pinfunction "+_+") (pintype "passive"))
      (node (ref "C43") (pin "1") (pinfunction "1_1") (pintype "passive"))
      (node (ref "C44") (pin "1") (pinfunction "1_1") (pintype "passive"))
      (node (ref "C45") (pin "1") (pinfunction "1_1") (pintype "passive"))
      (node (ref "C46") (pin "-") (pinfunction "-_-") (pintype "passive"))
      (node (ref "C47") (pin "-") (pinfunction "-_-") (pintype "passive"))
      (node (ref "C48") (pin "-") (pinfunction "-_-") (pintype "passive"))
      (node (ref "C49") (pin "-") (pinfunction "-_-") (pintype "passive"))
      (node (ref "C5") (pin "2") (pinfunction "2_2") (pintype "passive"))
      (node (ref "C50") (pin "-") (pinfunction "-_-") (pintype "passive"))
      (node (ref "C51") (pin "-") (pinfunction "-_-") (pintype "passive"))
      (node (ref "C52") (pin "-") (pinfunction "-_-") (pintype "passive"))
      (node (ref "C53") (pin "-") (pinfunction "-_-") (pintype "passive"))
      (node (ref "C54") (pin "+") (pinfunction "+_+") (pintype "passive"))
      (node (ref "C55") (pin "2") (pinfunction "2_2") (pintype "passive"))
      (node (ref "C56") (pin "-") (pinfunction "-_-") (pintype "passive"))
      (node (ref "C57") (pin "1") (pinfunction "1_1") (pintype "passive"))
      (node (ref "C58") (pin "-") (pinfunction "-_-") (pintype "passive"))
      (node (ref "C59") (pin "-") (pinfunction "-_-") (pintype "passive"))
      (node (ref "C6") (pin "2") (pinfunction "2_2") (pintype "passive"))
      (node (ref "C60") (pin "-") (pinfunction "-_-") (pintype "passive"))
      (node (ref "C61") (pin "-") (pinfunction "-_-") (pintype "passive"))
      (node (ref "C62") (pin "-") (pinfunction "-_-") (pintype "passive"))
      (node (ref "C63") (pin "-") (pinfunction "-_-") (pintype "passive"))
      (node (ref "C7") (pin "-") (pinfunction "-_-") (pintype "passive"))
      (node (ref "C8") (pin "+") (pinfunction "+_+") (pintype "passive"))
      (node (ref "D3") (pin "A") (pinfunction "A_A") (pintype "passive"))
      (node (ref "D5") (pin "A") (pinfunction "A_A") (pintype "passive"))
      (node (ref "D6") (pin "C") (pinfunction "C_C") (pintype "passive"))
      (node (ref "IC1") (pin "3") (pinfunction "GND_3") (pintype "power_in"))
      (node (ref "IC10") (pin "4") (pinfunction "V-_4") (pintype "power_in"))
      (node (ref "IC11") (pin "4") (pinfunction "V-_4") (pintype "power_in"))
      (node (ref "IC12") (pin "4") (pinfunction "V-_4") (pintype "power_in"))
      (node (ref "IC14") (pin "4") (pinfunction "V-_4") (pintype "power_in"))
      (node (ref "IC15") (pin "4") (pinfunction "V-_4") (pintype "power_in"))
      (node (ref "IC16") (pin "4") (pinfunction "V-_4") (pintype "power_in"))
      (node (ref "IC17") (pin "4") (pinfunction "V-_4") (pintype "power_in"))
      (node (ref "IC2") (pin "4") (pinfunction "V-_4") (pintype "power_in"))
      (node (ref "IC3") (pin "4") (pinfunction "V-_4") (pintype "power_in"))
      (node (ref "IC4") (pin "4") (pinfunction "V-_4") (pintype "power_in"))
      (node (ref "IC5") (pin "4") (pinfunction "V-_4") (pintype "power_in"))
      (node (ref "IC6") (pin "4") (pinfunction "V-_4") (pintype "power_in"))
      (node (ref "IC8") (pin "2") (pinfunction "GND_2") (pintype "passive"))
      (node (ref "J1") (pin "2") (pinfunction "2_2") (pintype "passive"))
      (node (ref "R21") (pin "1") (pinfunction "1_1") (pintype "passive"))
      (node (ref "R22") (pin "1") (pinfunction "1_1") (pintype "passive"))
      (node (ref "R24") (pin "1") (pinfunction "1_1") (pintype "passive"))
      (node (ref "R36") (pin "1") (pinfunction "1_1") (pintype "passive"))
      (node (ref "R37") (pin "1") (pinfunction "1_1") (pintype "passive"))
      (node (ref "R39") (pin "1") (pinfunction "1_1") (pintype "passive"))
      (node (ref "R48") (pin "1") (pinfunction "1_1") (pintype "passive"))
      (node (ref "R49") (pin "1") (pinfunction "1_1") (pintype "passive"))
      (node (ref "R5") (pin "2") (pinfunction "2_2") (pintype "passive"))
      (node (ref "R7") (pin "1") (pinfunction "1_1") (pintype "passive"))
    )
    (net (code "13") (name "Net-(+5V-PadA)") (class "Default")
      (node (ref "+5V") (pin "A") (pinfunction "A_A") (pintype "passive"))
      (node (ref "R14") (pin "1") (pinfunction "1_1") (pintype "passive"))
    )
    (net (code "14") (name "Net-(+9V-PadA)") (class "Default")
      (node (ref "+9V") (pin "A") (pinfunction "A_A") (pintype "passive"))
      (node (ref "R4") (pin "1") (pinfunction "1_1") (pintype "passive"))
    )
    (net (code "15") (name "Net-(-9V-PadA)") (class "Default")
      (node (ref "-9V") (pin "A") (pinfunction "A_A") (pintype "passive"))
      (node (ref "R5") (pin "1") (pinfunction "1_1") (pintype "passive"))
    )
    (net (code "16") (name "Net-(C1-Pad1)") (class "Default")
      (node (ref "C1") (pin "1") (pinfunction "1_1") (pintype "passive"))
      (node (ref "R8") (pin "1") (pinfunction "1_1") (pintype "passive"))
      (node (ref "R9") (pin "2") (pinfunction "2_2") (pintype "passive"))
    )
    (net (code "17") (name "Net-(C9-Pad1)") (class "Default")
      (node (ref "C9") (pin "1") (pinfunction "1_1") (pintype "passive"))
      (node (ref "R10") (pin "1") (pinfunction "1_1") (pintype "passive"))
      (node (ref "R11") (pin "2") (pinfunction "2_2") (pintype "passive"))
    )
    (net (code "18") (name "Net-(C16-Pad1)") (class "Default")
      (node (ref "C16") (pin "1") (pinfunction "1_1") (pintype "passive"))
      (node (ref "R25") (pin "1") (pinfunction "1_1") (pintype "passive"))
      (node (ref "R26") (pin "2") (pinfunction "2_2") (pintype "passive"))
    )
    (net (code "19") (name "Net-(C20-Pad1)") (class "Default")
      (node (ref "C20") (pin "1") (pinfunction "1_1") (pintype "passive"))
      (node (ref "R27") (pin "1") (pinfunction "1_1") (pintype "passive"))
      (node (ref "R28") (pin "2") (pinfunction "2_2") (pintype "passive"))
    )
    (net (code "20") (name "Net-(C27-Pad1)") (class "Default")
      (node (ref "C27") (pin "1") (pinfunction "1_1") (pintype "passive"))
      (node (ref "R40") (pin "1") (pinfunction "1_1") (pintype "passive"))
      (node (ref "R41") (pin "2") (pinfunction "2_2") (pintype "passive"))
    )
    (net (code "21") (name "Net-(C31-Pad1)") (class "Default")
      (node (ref "C31") (pin "1") (pinfunction "1_1") (pintype "passive"))
      (node (ref "R42") (pin "1") (pinfunction "1_1") (pintype "passive"))
      (node (ref "R43") (pin "2") (pinfunction "2_2") (pintype "passive"))
    )
    (net (code "22") (name "Net-(IC1-CAP+)") (class "Default")
      (node (ref "C2") (pin "+") (pinfunction "+_+") (pintype "passive"))
      (node (ref "IC1") (pin "2") (pinfunction "CAP+_2") (pintype "passive"))
    )
    (net (code "23") (name "Net-(IC1-CAP-)") (class "Default")
      (node (ref "C2") (pin "-") (pinfunction "-_-") (pintype "passive"))
      (node (ref "IC1") (pin "4") (pinfunction "CAP-_4") (pintype "passive"))
    )
    (net (code "24") (name "Net-(IC1-VIN)") (class "Default")
      (node (ref "7809L") (pin "IN") (pinfunction "IN_IN") (pintype "input"))
      (node (ref "C14") (pin "2") (pinfunction "2_2") (pintype "passive"))
      (node (ref "C15") (pin "+") (pinfunction "+_+") (pintype "passive"))
      (node (ref "C53") (pin "+") (pinfunction "+_+") (pintype "passive"))
      (node (ref "C57") (pin "2") (pinfunction "2_2") (pintype "passive"))
      (node (ref "C63") (pin "+") (pinfunction "+_+") (pintype "passive"))
      (node (ref "D1") (pin "C") (pinfunction "C_C") (pintype "passive"))
      (node (ref "D2") (pin "C") (pinfunction "C_C") (pintype "passive"))
      (node (ref "IC1") (pin "8") (pinfunction "VIN_8") (pintype "input"))
      (node (ref "IC8") (pin "3") (pinfunction "VI_3") (pintype "input"))
      (node (ref "J1") (pin "3") (pinfunction "3_3") (pintype "passive"))
    )
    (net (code "25") (name "Net-(IC1-VOUT)") (class "Default")
      (node (ref "7909L") (pin "IN") (pinfunction "IN_IN") (pintype "input"))
      (node (ref "C12") (pin "-") (pinfunction "-_-") (pintype "passive"))
      (node (ref "C54") (pin "-") (pinfunction "-_-") (pintype "passive"))
      (node (ref "C55") (pin "1") (pinfunction "1_1") (pintype "passive"))
      (node (ref "D4") (pin "A") (pinfunction "A_A") (pintype "passive"))
      (node (ref "IC1") (pin "5") (pinfunction "VOUT_5") (pintype "output"))
    )
    (net (code "26") (name "Net-(IC2-+IN)") (class "Default")
      (node (ref "C4") (pin "1") (pinfunction "1_1") (pintype "passive"))
      (node (ref "IC2") (pin "3") (pinfunction "+IN_3") (pintype "input"))
      (node (ref "R9") (pin "1") (pinfunction "1_1") (pintype "passive"))
    )
    (net (code "27") (name "Net-(IC2--IN)") (class "Default")
      (node (ref "C1") (pin "2") (pinfunction "2_2") (pintype "passive"))
      (node (ref "IC2") (pin "2") (pinfunction "-IN_2") (pintype "input"))
      (node (ref "IC2") (pin "6") (pinfunction "OUT_6") (pintype "output"))
      (node (ref "R10") (pin "2") (pinfunction "2_2") (pintype "passive"))
    )
    (net (code "28") (name "Net-(IC3-+IN)") (class "Default")
      (node (ref "IC3") (pin "3") (pinfunction "+IN_3") (pintype "input"))
      (node (ref "R6") (pin "1") (pinfunction "1_1") (pintype "passive"))
      (node (ref "R7") (pin "2") (pinfunction "2_2") (pintype "passive"))
    )
    (net (code "29") (name "Net-(IC3--IN)") (class "Default")
      (node (ref "C10") (pin "2") (pinfunction "2_2") (pintype "passive"))
      (node (ref "C4") (pin "2") (pinfunction "2_2") (pintype "passive"))
      (node (ref "IC3") (pin "2") (pinfunction "-IN_2") (pintype "input"))
      (node (ref "IC3") (pin "6") (pinfunction "OUT_6") (pintype "output"))
      (node (ref "IC7") (pin "7") (pinfunction "REF_7") (pintype "passive"))
      (node (ref "R12") (pin "2") (pinfunction "2_2") (pintype "passive"))
    )
    (net (code "30") (name "Net-(IC4-+IN)") (class "Default")
      (node (ref "C10") (pin "1") (pinfunction "1_1") (pintype "passive"))
      (node (ref "IC4") (pin "3") (pinfunction "+IN_3") (pintype "input"))
      (node (ref "R11") (pin "1") (pinfunction "1_1") (pintype "passive"))
    )
    (net (code "31") (name "Net-(IC4--IN)") (class "Default")
      (node (ref "C9") (pin "2") (pinfunction "2_2") (pintype "passive"))
      (node (ref "IC4") (pin "2") (pinfunction "-IN_2") (pintype "input"))
      (node (ref "IC4") (pin "6") (pinfunction "OUT_6") (pintype "output"))
      (node (ref "IC5") (pin "3") (pinfunction "+IN_3") (pintype "input"))
    )
    (net (code "32") (name "Net-(IC5--IN)") (class "Default")
      (node (ref "IC5") (pin "2") (pinfunction "-IN_2") (pintype "input"))
      (node (ref "R12") (pin "1") (pinfunction "1_1") (pintype "passive"))
      (node (ref "R13") (pin "2") (pinfunction "2_2") (pintype "passive"))
      (node (ref "R16") (pin "2") (pinfunction "2_2") (pintype "passive"))
      (node (ref "R17") (pin "2") (pinfunction "2_2") (pintype "passive"))
    )
    (net (code "33") (name "Net-(IC6-+IN)") (class "Default")
      (node (ref "C17") (pin "1") (pinfunction "1_1") (pintype "passive"))
      (node (ref "IC6") (pin "3") (pinfunction "+IN_3") (pintype "input"))
      (node (ref "R26") (pin "1") (pinfunction "1_1") (pintype "passive"))
    )
    (net (code "34") (name "Net-(IC6--IN)") (class "Default")
      (node (ref "C16") (pin "2") (pinfunction "2_2") (pintype "passive"))
      (node (ref "IC6") (pin "2") (pinfunction "-IN_2") (pintype "input"))
      (node (ref "IC6") (pin "6") (pinfunction "OUT_6") (pintype "output"))
      (node (ref "R27") (pin "2") (pinfunction "2_2") (pintype "passive"))
    )
    (net (code "35") (name "Net-(IC7-+GS)") (class "Default")
      (node (ref "IC7") (pin "2") (pinfunction "+GS_2") (pintype "input"))
      (node (ref "IC7") (pin "6") (pinfunction "+RG_6") (pintype "passive"))
      (node (ref "R1") (pin "1") (pinfunction "1_1") (pintype "passive"))
    )
    (net (code "36") (name "Net-(IC7-+IN)") (class "Default")
      (node (ref "IC7") (pin "1") (pinfunction "+IN_1") (pintype "input"))
      (node (ref "L2") (pin "2") (pinfunction "2_2") (pintype "passive"))
      (node (ref "R3") (pin "1") (pinfunction "1_1") (pintype "passive"))
    )
    (net (code "37") (name "Net-(IC7--GS)") (class "Default")
      (node (ref "IC7") (pin "13") (pinfunction "-RG_13") (pintype "passive"))
      (node (ref "IC7") (pin "15") (pinfunction "-GS_15") (pintype "input"))
      (node (ref "R1") (pin "2") (pinfunction "2_2") (pintype "passive"))
    )
    (net (code "38") (name "Net-(IC7--IN)") (class "Default")
      (node (ref "IC7") (pin "16") (pinfunction "-IN_16") (pintype "input"))
      (node (ref "L1") (pin "2") (pinfunction "2_2") (pintype "passive"))
      (node (ref "R2") (pin "1") (pinfunction "1_1") (pintype "passive"))
    )
    (net (code "39") (name "Net-(IC7-OUT)") (class "Default")
      (node (ref "IC7") (pin "10") (pinfunction "OUT_10") (pintype "output"))
      (node (ref "IC7") (pin "11") (pinfunction "SENSE_11") (pintype "input"))
      (node (ref "R8") (pin "2") (pinfunction "2_2") (pintype "passive"))
    )
    (net (code "40") (name "Net-(IC10-+IN)") (class "Default")
      (node (ref "IC10") (pin "3") (pinfunction "+IN_3") (pintype "input"))
      (node (ref "R23") (pin "1") (pinfunction "1_1") (pintype "passive"))
      (node (ref "R24") (pin "2") (pinfunction "2_2") (pintype "passive"))
    )
    (net (code "41") (name "Net-(IC10--IN)") (class "Default")
      (node (ref "C17") (pin "2") (pinfunction "2_2") (pintype "passive"))
      (node (ref "C21") (pin "2") (pinfunction "2_2") (pintype "passive"))
      (node (ref "IC10") (pin "2") (pinfunction "-IN_2") (pintype "input"))
      (node (ref "IC10") (pin "6") (pinfunction "OUT_6") (pintype "output"))
      (node (ref "IC13") (pin "7") (pinfunction "REF_7") (pintype "passive"))
      (node (ref "R29") (pin "2") (pinfunction "2_2") (pintype "passive"))
    )
    (net (code "42") (name "Net-(IC11-+IN)") (class "Default")
      (node (ref "C21") (pin "1") (pinfunction "1_1") (pintype "passive"))
      (node (ref "IC11") (pin "3") (pinfunction "+IN_3") (pintype "input"))
      (node (ref "R28") (pin "1") (pinfunction "1_1") (pintype "passive"))
    )
    (net (code "43") (name "Net-(IC11--IN)") (class "Default")
      (node (ref "C20") (pin "2") (pinfunction "2_2") (pintype "passive"))
      (node (ref "IC11") (pin "2") (pinfunction "-IN_2") (pintype "input"))
      (node (ref "IC11") (pin "6") (pinfunction "OUT_6") (pintype "output"))
      (node (ref "IC12") (pin "3") (pinfunction "+IN_3") (pintype "input"))
    )
    (net (code "44") (name "Net-(IC12--IN)") (class "Default")
      (node (ref "IC12") (pin "2") (pinfunction "-IN_2") (pintype "input"))
      (node (ref "R29") (pin "1") (pinfunction "1_1") (pintype "passive"))
      (node (ref "R30") (pin "2") (pinfunction "2_2") (pintype "passive"))
      (node (ref "R31") (pin "2") (pinfunction "2_2") (pintype "passive"))
      (node (ref "R32") (pin "2") (pinfunction "2_2") (pintype "passive"))
    )
    (net (code "45") (name "Net-(IC13-+GS)") (class "Default")
      (node (ref "IC13") (pin "2") (pinfunction "+GS_2") (pintype "input"))
      (node (ref "IC13") (pin "6") (pinfunction "+RG_6") (pintype "passive"))
      (node (ref "R18") (pin "1") (pinfunction "1_1") (pintype "passive"))
    )
    (net (code "46") (name "Net-(IC13-+IN)") (class "Default")
      (node (ref "IC13") (pin "1") (pinfunction "+IN_1") (pintype "input"))
      (node (ref "L4") (pin "2") (pinfunction "2_2") (pintype "passive"))
      (node (ref "R20") (pin "1") (pinfunction "1_1") (pintype "passive"))
    )
    (net (code "47") (name "Net-(IC13--GS)") (class "Default")
      (node (ref "IC13") (pin "13") (pinfunction "-RG_13") (pintype "passive"))
      (node (ref "IC13") (pin "15") (pinfunction "-GS_15") (pintype "input"))
      (node (ref "R18") (pin "2") (pinfunction "2_2") (pintype "passive"))
    )
    (net (code "48") (name "Net-(IC13--IN)") (class "Default")
      (node (ref "IC13") (pin "16") (pinfunction "-IN_16") (pintype "input"))
      (node (ref "L3") (pin "2") (pinfunction "2_2") (pintype "passive"))
      (node (ref "R19") (pin "1") (pinfunction "1_1") (pintype "passive"))
    )
    (net (code "49") (name "Net-(IC13-OUT)") (class "Default")
      (node (ref "IC13") (pin "10") (pinfunction "OUT_10") (pintype "output"))
      (node (ref "IC13") (pin "11") (pinfunction "SENSE_11") (pintype "input"))
      (node (ref "R25") (pin "2") (pinfunction "2_2") (pintype "passive"))
    )
    (net (code "50") (name "Net-(IC14-+IN)") (class "Default")
      (node (ref "C28") (pin "1") (pinfunction "1_1") (pintype "passive"))
      (node (ref "IC14") (pin "3") (pinfunction "+IN_3") (pintype "input"))
      (node (ref "R41") (pin "1") (pinfunction "1_1") (pintype "passive"))
    )
    (net (code "51") (name "Net-(IC14--IN)") (class "Default")
      (node (ref "C27") (pin "2") (pinfunction "2_2") (pintype "passive"))
      (node (ref "IC14") (pin "2") (pinfunction "-IN_2") (pintype "input"))
      (node (ref "IC14") (pin "6") (pinfunction "OUT_6") (pintype "output"))
      (node (ref "R42") (pin "2") (pinfunction "2_2") (pintype "passive"))
    )
    (net (code "52") (name "Net-(IC15-+IN)") (class "Default")
      (node (ref "IC15") (pin "3") (pinfunction "+IN_3") (pintype "input"))
      (node (ref "R38") (pin "1") (pinfunction "1_1") (pintype "passive"))
      (node (ref "R39") (pin "2") (pinfunction "2_2") (pintype "passive"))
    )
    (net (code "53") (name "Net-(IC15--IN)") (class "Default")
      (node (ref "C28") (pin "2") (pinfunction "2_2") (pintype "passive"))
      (node (ref "C32") (pin "2") (pinfunction "2_2") (pintype "passive"))
      (node (ref "IC15") (pin "2") (pinfunction "-IN_2") (pintype "input"))
      (node (ref "IC15") (pin "6") (pinfunction "OUT_6") (pintype "output"))
      (node (ref "IC18") (pin "7") (pinfunction "REF_7") (pintype "passive"))
      (node (ref "R44") (pin "2") (pinfunction "2_2") (pintype "passive"))
    )
    (net (code "54") (name "Net-(IC16-+IN)") (class "Default")
      (node (ref "C32") (pin "1") (pinfunction "1_1") (pintype "passive"))
      (node (ref "IC16") (pin "3") (pinfunction "+IN_3") (pintype "input"))
      (node (ref "R43") (pin "1") (pinfunction "1_1") (pintype "passive"))
    )
    (net (code "55") (name "Net-(IC16--IN)") (class "Default")
      (node (ref "C31") (pin "2") (pinfunction "2_2") (pintype "passive"))
      (node (ref "IC16") (pin "2") (pinfunction "-IN_2") (pintype "input"))
      (node (ref "IC16") (pin "6") (pinfunction "OUT_6") (pintype "output"))
      (node (ref "IC17") (pin "3") (pinfunction "+IN_3") (pintype "input"))
    )
    (net (code "56") (name "Net-(IC17--IN)") (class "Default")
      (node (ref "IC17") (pin "2") (pinfunction "-IN_2") (pintype "input"))
      (node (ref "R44") (pin "1") (pinfunction "1_1") (pintype "passive"))
      (node (ref "R45") (pin "2") (pinfunction "2_2") (pintype "passive"))
      (node (ref "R46") (pin "2") (pinfunction "2_2") (pintype "passive"))
      (node (ref "R47") (pin "2") (pinfunction "2_2") (pintype "passive"))
    )
    (net (code "57") (name "Net-(IC18-+GS)") (class "Default")
      (node (ref "IC18") (pin "2") (pinfunction "+GS_2") (pintype "input"))
      (node (ref "IC18") (pin "6") (pinfunction "+RG_6") (pintype "passive"))
      (node (ref "R33") (pin "1") (pinfunction "1_1") (pintype "passive"))
    )
    (net (code "58") (name "Net-(IC18-+IN)") (class "Default")
      (node (ref "IC18") (pin "1") (pinfunction "+IN_1") (pintype "input"))
      (node (ref "L6") (pin "2") (pinfunction "2_2") (pintype "passive"))
      (node (ref "R35") (pin "1") (pinfunction "1_1") (pintype "passive"))
    )
    (net (code "59") (name "Net-(IC18--GS)") (class "Default")
      (node (ref "IC18") (pin "13") (pinfunction "-RG_13") (pintype "passive"))
      (node (ref "IC18") (pin "15") (pinfunction "-GS_15") (pintype "input"))
      (node (ref "R33") (pin "2") (pinfunction "2_2") (pintype "passive"))
    )
    (net (code "60") (name "Net-(IC18--IN)") (class "Default")
      (node (ref "IC18") (pin "16") (pinfunction "-IN_16") (pintype "input"))
      (node (ref "L5") (pin "2") (pinfunction "2_2") (pintype "passive"))
      (node (ref "R34") (pin "1") (pinfunction "1_1") (pintype "passive"))
    )
    (net (code "61") (name "Net-(IC18-OUT)") (class "Default")
      (node (ref "IC18") (pin "10") (pinfunction "OUT_10") (pintype "output"))
      (node (ref "IC18") (pin "11") (pinfunction "SENSE_11") (pintype "input"))
      (node (ref "R40") (pin "2") (pinfunction "2_2") (pintype "passive"))
    )
    (net (code "62") (name "Net-(JP1-Pad1)") (class "Default")
      (node (ref "JP1") (pin "1") (pinfunction "1_1") (pintype "passive"))
      (node (ref "R13") (pin "1") (pinfunction "1_1") (pintype "passive"))
    )
    (net (code "63") (name "Net-(JP2-Pad1)") (class "Default")
      (node (ref "JP2") (pin "1") (pinfunction "1_1") (pintype "passive"))
      (node (ref "R16") (pin "1") (pinfunction "1_1") (pintype "passive"))
    )
    (net (code "64") (name "Net-(JP3-Pad1)") (class "Default")
      (node (ref "JP3") (pin "1") (pinfunction "1_1") (pintype "passive"))
      (node (ref "R17") (pin "1") (pinfunction "1_1") (pintype "passive"))
    )
    (net (code "65") (name "Net-(JP4-Pad1)") (class "Default")
      (node (ref "JP4") (pin "1") (pinfunction "1_1") (pintype "passive"))
      (node (ref "R30") (pin "1") (pinfunction "1_1") (pintype "passive"))
    )
    (net (code "66") (name "Net-(JP5-Pad1)") (class "Default")
      (node (ref "JP5") (pin "1") (pinfunction "1_1") (pintype "passive"))
      (node (ref "R31") (pin "1") (pinfunction "1_1") (pintype "passive"))
    )
    (net (code "67") (name "Net-(JP6-Pad1)") (class "Default")
      (node (ref "JP6") (pin "1") (pinfunction "1_1") (pintype "passive"))
      (node (ref "R32") (pin "1") (pinfunction "1_1") (pintype "passive"))
    )
    (net (code "68") (name "Net-(JP7-Pad1)") (class "Default")
      (node (ref "JP7") (pin "1") (pinfunction "1_1") (pintype "passive"))
      (node (ref "R45") (pin "1") (pinfunction "1_1") (pintype "passive"))
    )
    (net (code "69") (name "Net-(JP8-Pad1)") (class "Default")
      (node (ref "JP8") (pin "1") (pinfunction "1_1") (pintype "passive"))
      (node (ref "R46") (pin "1") (pinfunction "1_1") (pintype "passive"))
    )
    (net (code "70") (name "Net-(JP9-Pad1)") (class "Default")
      (node (ref "JP9") (pin "1") (pinfunction "1_1") (pintype "passive"))
      (node (ref "R47") (pin "1") (pinfunction "1_1") (pintype "passive"))
    )
    (net (code "71") (name "VCC") (class "Default")
      (node (ref "C11") (pin "1") (pinfunction "1_1") (pintype "passive"))
      (node (ref "C13") (pin "1") (pinfunction "1_1") (pintype "passive"))
      (node (ref "C22") (pin "1") (pinfunction "1_1") (pintype "passive"))
      (node (ref "C23") (pin "1") (pinfunction "1_1") (pintype "passive"))
      (node (ref "C24") (pin "2") (pinfunction "2_2") (pintype "passive"))
      (node (ref "C25") (pin "1") (pinfunction "1_1") (pintype "passive"))
      (node (ref "C26") (pin "1") (pinfunction "1_1") (pintype "passive"))
      (node (ref "C34") (pin "1") (pinfunction "1_1") (pintype "passive"))
      (node (ref "C35") (pin "1") (pinfunction "1_1") (pintype "passive"))
      (node (ref "C36") (pin "1") (pinfunction "1_1") (pintype "passive"))
      (node (ref "C37") (pin "1") (pinfunction "1_1") (pintype "passive"))
      (node (ref "C46") (pin "+") (pinfunction "+_+") (pintype "passive"))
      (node (ref "C47") (pin "+") (pinfunction "+_+") (pintype "passive"))
      (node (ref "C48") (pin "+") (pinfunction "+_+") (pintype "passive"))
      (node (ref "C49") (pin "+") (pinfunction "+_+") (pintype "passive"))
      (node (ref "C5") (pin "1") (pinfunction "1_1") (pintype "passive"))
      (node (ref "C50") (pin "+") (pinfunction "+_+") (pintype "passive"))
      (node (ref "C51") (pin "+") (pinfunction "+_+") (pintype "passive"))
      (node (ref "C52") (pin "+") (pinfunction "+_+") (pintype "passive"))
      (node (ref "C56") (pin "+") (pinfunction "+_+") (pintype "passive"))
      (node (ref "C58") (pin "+") (pinfunction "+_+") (pintype "passive"))
      (node (ref "C59") (pin "+") (pinfunction "+_+") (pintype "passive"))
      (node (ref "C6") (pin "1") (pinfunction "1_1") (pintype "passive"))
      (node (ref "C60") (pin "+") (pinfunction "+_+") (pintype "passive"))
      (node (ref "C61") (pin "+") (pinfunction "+_+") (pintype "passive"))
      (node (ref "C62") (pin "+") (pinfunction "+_+") (pintype "passive"))
      (node (ref "D2") (pin "A") (pinfunction "A_A") (pintype "passive"))
      (node (ref "D3") (pin "C") (pinfunction "C_C") (pintype "passive"))
      (node (ref "IC10") (pin "7") (pinfunction "V+_7") (pintype "power_in"))
      (node (ref "IC11") (pin "7") (pinfunction "V+_7") (pintype "power_in"))
      (node (ref "IC12") (pin "7") (pinfunction "V+_7") (pintype "power_in"))
      (node (ref "IC14") (pin "7") (pinfunction "V+_7") (pintype "power_in"))
      (node (ref "IC15") (pin "7") (pinfunction "V+_7") (pintype "power_in"))
      (node (ref "IC16") (pin "7") (pinfunction "V+_7") (pintype "power_in"))
      (node (ref "IC17") (pin "7") (pinfunction "V+_7") (pintype "power_in"))
      (node (ref "IC2") (pin "7") (pinfunction "V+_7") (pintype "power_in"))
      (node (ref "IC3") (pin "7") (pinfunction "V+_7") (pintype "power_in"))
      (node (ref "IC4") (pin "7") (pinfunction "V+_7") (pintype "power_in"))
      (node (ref "IC5") (pin "7") (pinfunction "V+_7") (pintype "power_in"))
      (node (ref "IC6") (pin "7") (pinfunction "V+_7") (pintype "power_in"))
      (node (ref "IC8") (pin "1") (pinfunction "VO_1") (pintype "passive"))
      (node (ref "R14") (pin "2") (pinfunction "2_2") (pintype "passive"))
      (node (ref "R23") (pin "2") (pinfunction "2_2") (pintype "passive"))
      (node (ref "R38") (pin "2") (pinfunction "2_2") (pintype "passive"))
      (node (ref "R6") (pin "2") (pinfunction "2_2") (pintype "passive"))
    )
    (net (code "72") (name "unconnected-(ASPOUT-Pad4)") (class "Default")
      (node (ref "ASPOUT") (pin "4") (pinfunction "4_4") (pintype "passive"))
    )
    (net (code "73") (name "unconnected-(GEOIN-Pad7)") (class "Default")
      (node (ref "GEOIN") (pin "7") (pinfunction "7_7") (pintype "passive"))
    )
    (net (code "74") (name "unconnected-(GEOIN-Pad8)") (class "Default")
      (node (ref "GEOIN") (pin "8") (pinfunction "8_8") (pintype "passive"))
    )
    (net (code "75") (name "unconnected-(GEOIN-Pad9)") (class "Default")
      (node (ref "GEOIN") (pin "9") (pinfunction "9_9") (pintype "passive"))
    )
    (net (code "76") (name "unconnected-(GEOIN-Pad10)") (class "Default")
      (node (ref "GEOIN") (pin "10") (pinfunction "10_10") (pintype "passive"))
    )
    (net (code "77") (name "unconnected-(IC1-FB-Pad1)") (class "Default")
      (node (ref "IC1") (pin "1") (pinfunction "FB_1") (pintype "input"))
    )
    (net (code "78") (name "unconnected-(IC1-OSC-Pad7)") (class "Default")
      (node (ref "IC1") (pin "7") (pinfunction "OSC_7") (pintype "output"))
    )
    (net (code "79") (name "unconnected-(IC1-REF-Pad6)") (class "Default")
      (node (ref "IC1") (pin "6") (pinfunction "REF_6") (pintype "input"))
    )
    (net (code "80") (name "unconnected-(IC2-OFF1-Pad1)") (class "Default")
      (node (ref "IC2") (pin "1") (pinfunction "OFF1_1") (pintype "passive"))
    )
    (net (code "81") (name "unconnected-(IC2-OFF2-Pad8)") (class "Default")
      (node (ref "IC2") (pin "8") (pinfunction "OFF2_8") (pintype "passive"))
    )
    (net (code "82") (name "unconnected-(IC3-OFF1-Pad1)") (class "Default")
      (node (ref "IC3") (pin "1") (pinfunction "OFF1_1") (pintype "passive"))
    )
    (net (code "83") (name "unconnected-(IC3-OFF2-Pad8)") (class "Default")
      (node (ref "IC3") (pin "8") (pinfunction "OFF2_8") (pintype "passive"))
    )
    (net (code "84") (name "unconnected-(IC4-OFF1-Pad1)") (class "Default")
      (node (ref "IC4") (pin "1") (pinfunction "OFF1_1") (pintype "passive"))
    )
    (net (code "85") (name "unconnected-(IC4-OFF2-Pad8)") (class "Default")
      (node (ref "IC4") (pin "8") (pinfunction "OFF2_8") (pintype "passive"))
    )
    (net (code "86") (name "unconnected-(IC5-OFF1-Pad1)") (class "Default")
      (node (ref "IC5") (pin "1") (pinfunction "OFF1_1") (pintype "passive"))
    )
    (net (code "87") (name "unconnected-(IC5-OFF2-Pad8)") (class "Default")
      (node (ref "IC5") (pin "8") (pinfunction "OFF2_8") (pintype "passive"))
    )
    (net (code "88") (name "unconnected-(IC6-OFF1-Pad1)") (class "Default")
      (node (ref "IC6") (pin "1") (pinfunction "OFF1_1") (pintype "passive"))
    )
    (net (code "89") (name "unconnected-(IC6-OFF2-Pad8)") (class "Default")
      (node (ref "IC6") (pin "8") (pinfunction "OFF2_8") (pintype "passive"))
    )
    (net (code "90") (name "unconnected-(IC7-+GD-Pad5)") (class "Default")
      (node (ref "IC7") (pin "5") (pinfunction "+GD_5") (pintype "passive"))
    )
    (net (code "91") (name "unconnected-(IC7-+OFFS-Pad3)") (class "Default")
      (node (ref "IC7") (pin "3") (pinfunction "+OFFS_3") (pintype "passive"))
    )
    (net (code "92") (name "unconnected-(IC7--GD-Pad12)") (class "Default")
      (node (ref "IC7") (pin "12") (pinfunction "-GD_12") (pintype "passive"))
    )
    (net (code "93") (name "unconnected-(IC7--OFFS-Pad4)") (class "Default")
      (node (ref "IC7") (pin "4") (pinfunction "-OFFS_4") (pintype "passive"))
    )
    (net (code "94") (name "unconnected-(IC7-G=100-Pad14)") (class "Default")
      (node (ref "IC7") (pin "14") (pinfunction "G=100_14") (pintype "passive"))
    )
    (net (code "95") (name "unconnected-(IC10-OFF1-Pad1)") (class "Default")
      (node (ref "IC10") (pin "1") (pinfunction "OFF1_1") (pintype "passive"))
    )
    (net (code "96") (name "unconnected-(IC10-OFF2-Pad8)") (class "Default")
      (node (ref "IC10") (pin "8") (pinfunction "OFF2_8") (pintype "passive"))
    )
    (net (code "97") (name "unconnected-(IC11-OFF1-Pad1)") (class "Default")
      (node (ref "IC11") (pin "1") (pinfunction "OFF1_1") (pintype "passive"))
    )
    (net (code "98") (name "unconnected-(IC11-OFF2-Pad8)") (class "Default")
      (node (ref "IC11") (pin "8") (pinfunction "OFF2_8") (pintype "passive"))
    )
    (net (code "99") (name "unconnected-(IC12-OFF1-Pad1)") (class "Default")
      (node (ref "IC12") (pin "1") (pinfunction "OFF1_1") (pintype "passive"))
    )
    (net (code "100") (name "unconnected-(IC12-OFF2-Pad8)") (class "Default")
      (node (ref "IC12") (pin "8") (pinfunction "OFF2_8") (pintype "passive"))
    )
    (net (code "101") (name "unconnected-(IC13-+GD-Pad5)") (class "Default")
      (node (ref "IC13") (pin "5") (pinfunction "+GD_5") (pintype "passive"))
    )
    (net (code "102") (name "unconnected-(IC13-+OFFS-Pad3)") (class "Default")
      (node (ref "IC13") (pin "3") (pinfunction "+OFFS_3") (pintype "passive"))
    )
    (net (code "103") (name "unconnected-(IC13--GD-Pad12)") (class "Default")
      (node (ref "IC13") (pin "12") (pinfunction "-GD_12") (pintype "passive"))
    )
    (net (code "104") (name "unconnected-(IC13--OFFS-Pad4)") (class "Default")
      (node (ref "IC13") (pin "4") (pinfunction "-OFFS_4") (pintype "passive"))
    )
    (net (code "105") (name "unconnected-(IC13-G=100-Pad14)") (class "Default")
      (node (ref "IC13") (pin "14") (pinfunction "G=100_14") (pintype "passive"))
    )
    (net (code "106") (name "unconnected-(IC14-OFF1-Pad1)") (class "Default")
      (node (ref "IC14") (pin "1") (pinfunction "OFF1_1") (pintype "passive"))
    )
    (net (code "107") (name "unconnected-(IC14-OFF2-Pad8)") (class "Default")
      (node (ref "IC14") (pin "8") (pinfunction "OFF2_8") (pintype "passive"))
    )
    (net (code "108") (name "unconnected-(IC15-OFF1-Pad1)") (class "Default")
      (node (ref "IC15") (pin "1") (pinfunction "OFF1_1") (pintype "passive"))
    )
    (net (code "109") (name "unconnected-(IC15-OFF2-Pad8)") (class "Default")
      (node (ref "IC15") (pin "8") (pinfunction "OFF2_8") (pintype "passive"))
    )
    (net (code "110") (name "unconnected-(IC16-OFF1-Pad1)") (class "Default")
      (node (ref "IC16") (pin "1") (pinfunction "OFF1_1") (pintype "passive"))
    )
    (net (code "111") (name "unconnected-(IC16-OFF2-Pad8)") (class "Default")
      (node (ref "IC16") (pin "8") (pinfunction "OFF2_8") (pintype "passive"))
    )
    (net (code "112") (name "unconnected-(IC17-OFF1-Pad1)") (class "Default")
      (node (ref "IC17") (pin "1") (pinfunction "OFF1_1") (pintype "passive"))
    )
    (net (code "113") (name "unconnected-(IC17-OFF2-Pad8)") (class "Default")
      (node (ref "IC17") (pin "8") (pinfunction "OFF2_8") (pintype "passive"))
    )
    (net (code "114") (name "unconnected-(IC18-+GD-Pad5)") (class "Default")
      (node (ref "IC18") (pin "5") (pinfunction "+GD_5") (pintype "passive"))
    )
    (net (code "115") (name "unconnected-(IC18-+OFFS-Pad3)") (class "Default")
      (node (ref "IC18") (pin "3") (pinfunction "+OFFS_3") (pintype "passive"))
    )
    (net (code "116") (name "unconnected-(IC18--GD-Pad12)") (class "Default")
      (node (ref "IC18") (pin "12") (pinfunction "-GD_12") (pintype "passive"))
    )
    (net (code "117") (name "unconnected-(IC18--OFFS-Pad4)") (class "Default")
      (node (ref "IC18") (pin "4") (pinfunction "-OFFS_4") (pintype "passive"))
    )
    (net (code "118") (name "unconnected-(IC18-G=100-Pad14)") (class "Default")
      (node (ref "IC18") (pin "14") (pinfunction "G=100_14") (pintype "passive"))
    )
    (net (code "119") (name "unconnected-(J1-Pad1)") (class "Default")
      (node (ref "J1") (pin "1") (pinfunction "1_1") (pintype "passive"))
    )
    (net (code "120") (name "unconnected-(J1-Pad4)") (class "Default")
      (node (ref "J1") (pin "4") (pinfunction "4_4") (pintype "passive"))
    )
  )
)
